# JunctionBoard.net
KiCad netlist of a schematic drawn in EAGLE
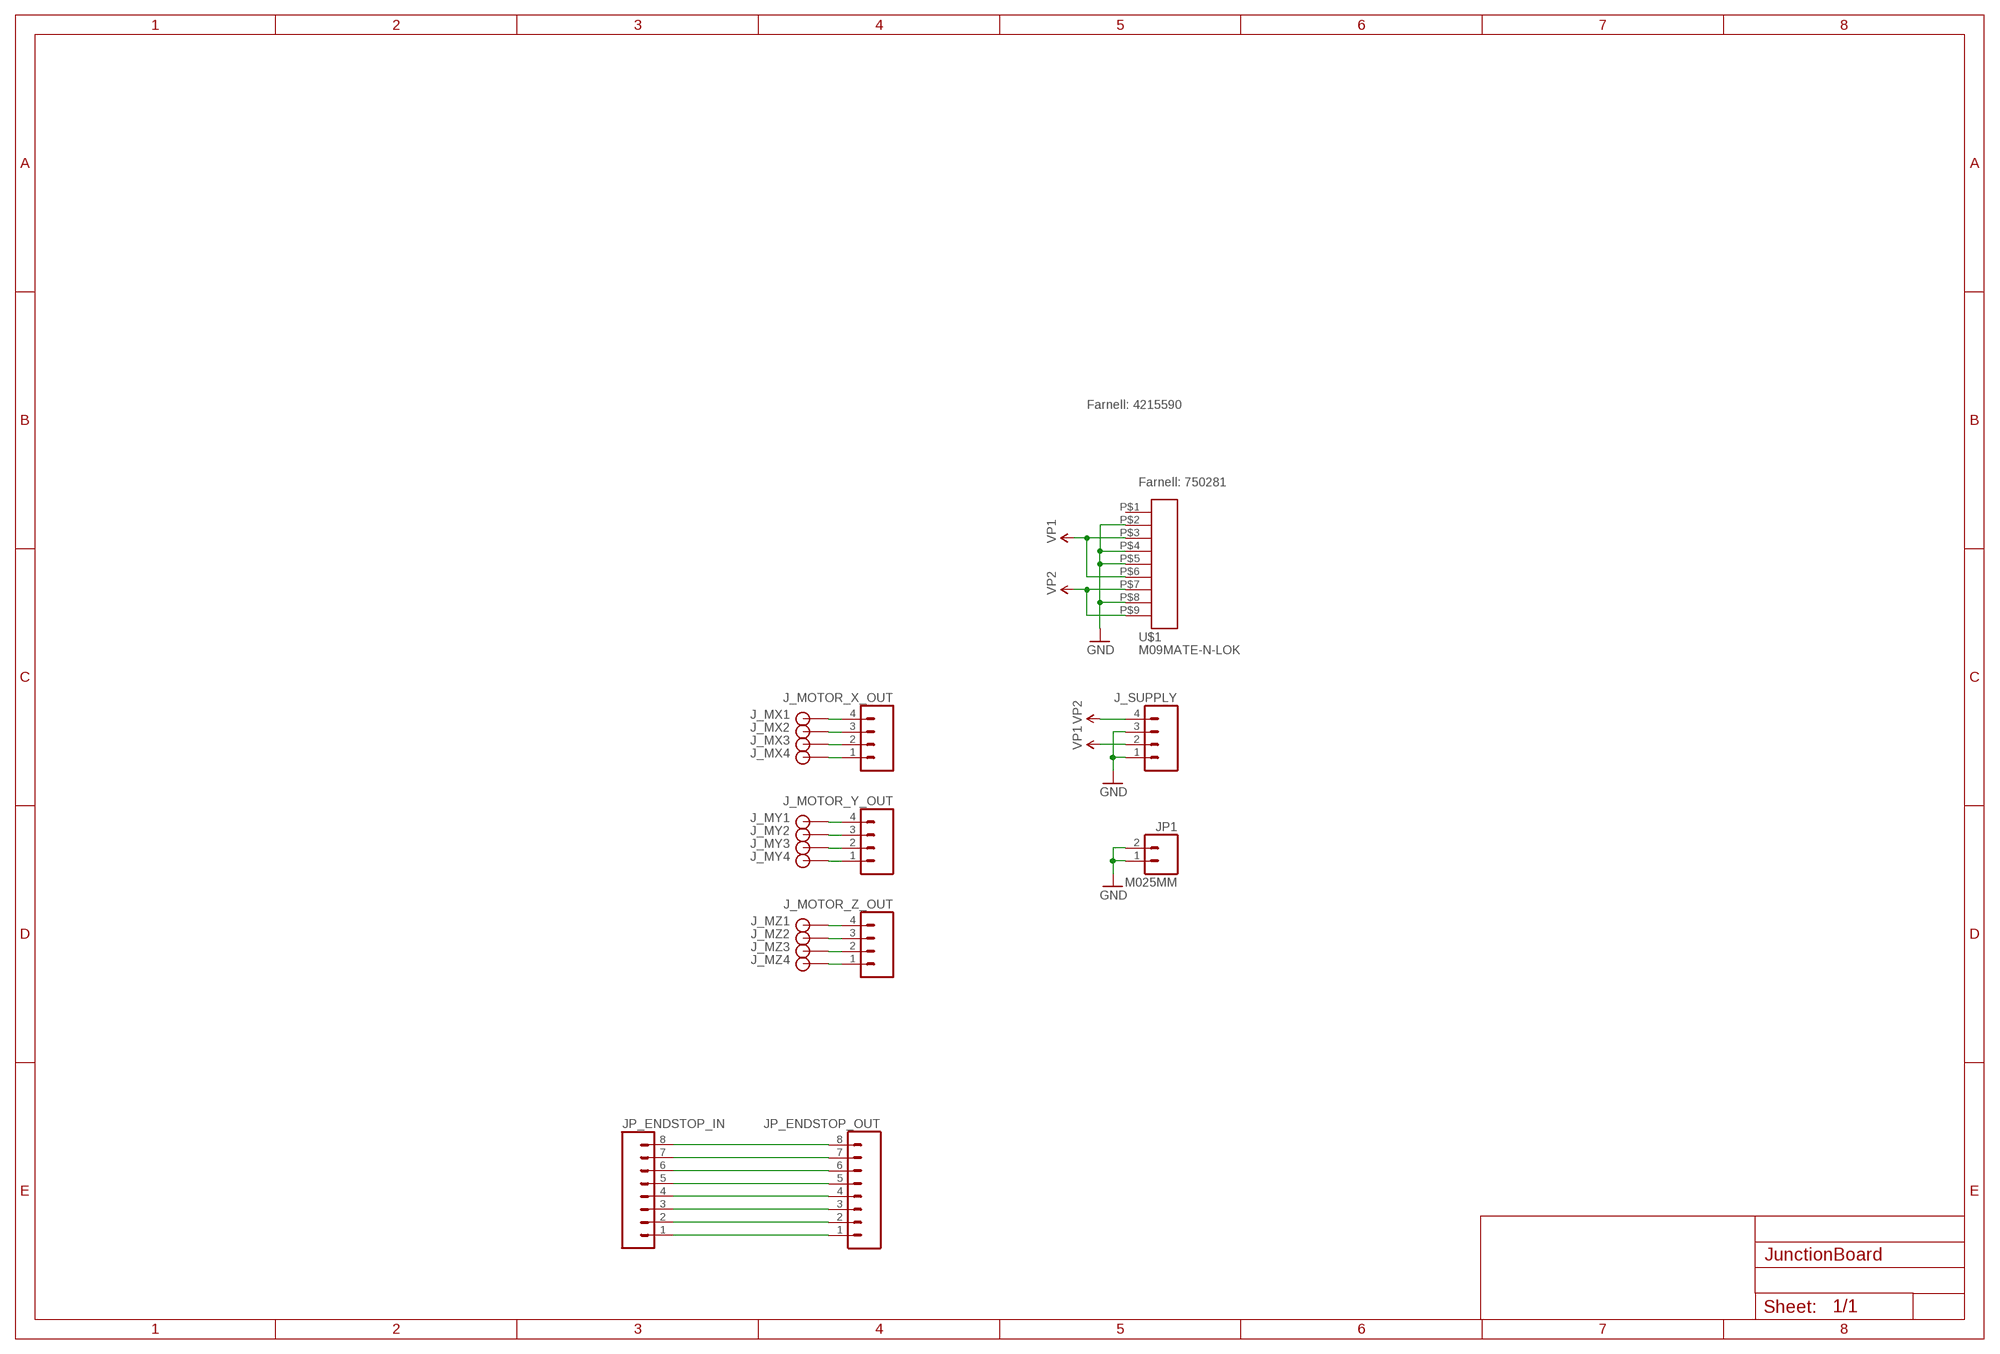
[diagram p0: schematic, sheet 1]

(export (version "E")
  (design (tool "Eeschema 10.0.6"))
  (components
    (comp (ref "JP1")
      (value "M025MM")
      (footprint "eagle-import:SCREWTERMINAL-5MM-2")
      (libsource (lib "eagle-import") (part "M025MM"))
    )
    (comp (ref "JP_ENDSTOP_IN")
      (value "M083.5MM-8")
      (footprint "eagle-import:SCREWTERMINAL-3.5MM-8")
      (libsource (lib "eagle-import") (part "M083.5MM-8"))
    )
    (comp (ref "JP_ENDSTOP_OUT")
      (value "M083.5MM-8")
      (footprint "eagle-import:SCREWTERMINAL-3.5MM-8")
      (libsource (lib "eagle-import") (part "M083.5MM-8"))
    )
    (comp (ref "J_MOTOR_X_OUT")
      (value "M04SCREW5")
      (footprint "eagle-import:SCREWTERMINAL-5MM-4")
      (libsource (lib "eagle-import") (part "M04SCREW5"))
    )
    (comp (ref "J_MOTOR_Y_OUT")
      (value "M04SCREW5")
      (footprint "eagle-import:SCREWTERMINAL-5MM-4")
      (libsource (lib "eagle-import") (part "M04SCREW5"))
    )
    (comp (ref "J_MOTOR_Z_OUT")
      (value "M04SCREW5")
      (footprint "eagle-import:SCREWTERMINAL-5MM-4")
      (libsource (lib "eagle-import") (part "M04SCREW5"))
    )
    (comp (ref "J_MX1")
      (value "M01")
      (footprint "eagle-import:FASTON-1")
      (libsource (lib "eagle-import") (part "M01"))
    )
    (comp (ref "J_MX2")
      (value "M01")
      (footprint "eagle-import:FASTON-1")
      (libsource (lib "eagle-import") (part "M01"))
    )
    (comp (ref "J_MX3")
      (value "M01")
      (footprint "eagle-import:FASTON-1")
      (libsource (lib "eagle-import") (part "M01"))
    )
    (comp (ref "J_MX4")
      (value "M01")
      (footprint "eagle-import:FASTON-1")
      (libsource (lib "eagle-import") (part "M01"))
    )
    (comp (ref "J_MY1")
      (value "M01")
      (footprint "eagle-import:FASTON-1")
      (libsource (lib "eagle-import") (part "M01"))
    )
    (comp (ref "J_MY2")
      (value "M01")
      (footprint "eagle-import:FASTON-1")
      (libsource (lib "eagle-import") (part "M01"))
    )
    (comp (ref "J_MY3")
      (value "M01")
      (footprint "eagle-import:FASTON-1")
      (libsource (lib "eagle-import") (part "M01"))
    )
    (comp (ref "J_MY4")
      (value "M01")
      (footprint "eagle-import:FASTON-1")
      (libsource (lib "eagle-import") (part "M01"))
    )
    (comp (ref "J_MZ1")
      (value "M01")
      (footprint "eagle-import:FASTON-1")
      (libsource (lib "eagle-import") (part "M01"))
    )
    (comp (ref "J_MZ2")
      (value "M01")
      (footprint "eagle-import:FASTON-1")
      (libsource (lib "eagle-import") (part "M01"))
    )
    (comp (ref "J_MZ3")
      (value "M01")
      (footprint "eagle-import:FASTON-1")
      (libsource (lib "eagle-import") (part "M01"))
    )
    (comp (ref "J_MZ4")
      (value "M01")
      (footprint "eagle-import:FASTON-1")
      (libsource (lib "eagle-import") (part "M01"))
    )
    (comp (ref "J_SUPPLY")
      (value "M04SCREW5")
      (footprint "eagle-import:SCREWTERMINAL-5MM-4")
      (libsource (lib "eagle-import") (part "M04SCREW5"))
    )
    (comp (ref "U$1")
      (value "M09MATE-N-LOK")
      (footprint "eagle-import:MATE-N-LOK-9")
      (libsource (lib "eagle-import") (part "M09MATE-N-LOK"))
    )
  )
  (nets
    (net (code "1") (name "GND") (class "Default")
      (node (ref "JP1") (pin "1") (pinfunction "1_1") (pintype "passive"))
      (node (ref "JP1") (pin "2") (pinfunction "2_2") (pintype "passive"))
      (node (ref "J_SUPPLY") (pin "1") (pinfunction "1_1") (pintype "passive"))
      (node (ref "J_SUPPLY") (pin "3") (pinfunction "3_3") (pintype "passive"))
      (node (ref "U$1") (pin "P$2") (pinfunction "P$2_P$2") (pintype "bidirectional"))
      (node (ref "U$1") (pin "P$4") (pinfunction "P$4_P$4") (pintype "bidirectional"))
      (node (ref "U$1") (pin "P$5") (pinfunction "P$5_P$5") (pintype "bidirectional"))
      (node (ref "U$1") (pin "P$8") (pinfunction "P$8_P$8") (pintype "bidirectional"))
    )
    (net (code "2") (name "Net-(JP_ENDSTOP_IN-Pad1)") (class "Default")
      (node (ref "JP_ENDSTOP_IN") (pin "1") (pinfunction "1_1") (pintype "passive"))
      (node (ref "JP_ENDSTOP_OUT") (pin "1") (pinfunction "1_1") (pintype "passive"))
    )
    (net (code "3") (name "Net-(JP_ENDSTOP_IN-Pad2)") (class "Default")
      (node (ref "JP_ENDSTOP_IN") (pin "2") (pinfunction "2_2") (pintype "passive"))
      (node (ref "JP_ENDSTOP_OUT") (pin "2") (pinfunction "2_2") (pintype "passive"))
    )
    (net (code "4") (name "Net-(JP_ENDSTOP_IN-Pad3)") (class "Default")
      (node (ref "JP_ENDSTOP_IN") (pin "3") (pinfunction "3_3") (pintype "passive"))
      (node (ref "JP_ENDSTOP_OUT") (pin "3") (pinfunction "3_3") (pintype "passive"))
    )
    (net (code "5") (name "Net-(JP_ENDSTOP_IN-Pad4)") (class "Default")
      (node (ref "JP_ENDSTOP_IN") (pin "4") (pinfunction "4_4") (pintype "passive"))
      (node (ref "JP_ENDSTOP_OUT") (pin "4") (pinfunction "4_4") (pintype "passive"))
    )
    (net (code "6") (name "Net-(JP_ENDSTOP_IN-Pad5)") (class "Default")
      (node (ref "JP_ENDSTOP_IN") (pin "5") (pinfunction "5_5") (pintype "passive"))
      (node (ref "JP_ENDSTOP_OUT") (pin "5") (pinfunction "5_5") (pintype "passive"))
    )
    (net (code "7") (name "Net-(JP_ENDSTOP_IN-Pad6)") (class "Default")
      (node (ref "JP_ENDSTOP_IN") (pin "6") (pinfunction "6_6") (pintype "passive"))
      (node (ref "JP_ENDSTOP_OUT") (pin "6") (pinfunction "6_6") (pintype "passive"))
    )
    (net (code "8") (name "Net-(JP_ENDSTOP_IN-Pad7)") (class "Default")
      (node (ref "JP_ENDSTOP_IN") (pin "7") (pinfunction "7_7") (pintype "passive"))
      (node (ref "JP_ENDSTOP_OUT") (pin "7") (pinfunction "7_7") (pintype "passive"))
    )
    (net (code "9") (name "Net-(JP_ENDSTOP_IN-Pad8)") (class "Default")
      (node (ref "JP_ENDSTOP_IN") (pin "8") (pinfunction "8_8") (pintype "passive"))
      (node (ref "JP_ENDSTOP_OUT") (pin "8") (pinfunction "8_8") (pintype "passive"))
    )
    (net (code "10") (name "Net-(J_MOTOR_X_OUT-Pad1)") (class "Default")
      (node (ref "J_MOTOR_X_OUT") (pin "1") (pinfunction "1_1") (pintype "passive"))
      (node (ref "J_MX4") (pin "P$1") (pinfunction "P$1_P$1") (pintype "bidirectional"))
      (node (ref "J_MX4") (pin "P$2") (pinfunction "P$1_P$2") (pintype "bidirectional"))
    )
    (net (code "11") (name "Net-(J_MOTOR_X_OUT-Pad2)") (class "Default")
      (node (ref "J_MOTOR_X_OUT") (pin "2") (pinfunction "2_2") (pintype "passive"))
      (node (ref "J_MX3") (pin "P$1") (pinfunction "P$1_P$1") (pintype "bidirectional"))
      (node (ref "J_MX3") (pin "P$2") (pinfunction "P$1_P$2") (pintype "bidirectional"))
    )
    (net (code "12") (name "Net-(J_MOTOR_X_OUT-Pad3)") (class "Default")
      (node (ref "J_MOTOR_X_OUT") (pin "3") (pinfunction "3_3") (pintype "passive"))
      (node (ref "J_MX2") (pin "P$1") (pinfunction "P$1_P$1") (pintype "bidirectional"))
      (node (ref "J_MX2") (pin "P$2") (pinfunction "P$1_P$2") (pintype "bidirectional"))
    )
    (net (code "13") (name "Net-(J_MOTOR_X_OUT-Pad4)") (class "Default")
      (node (ref "J_MOTOR_X_OUT") (pin "4") (pinfunction "4_4") (pintype "passive"))
      (node (ref "J_MX1") (pin "P$1") (pinfunction "P$1_P$1") (pintype "bidirectional"))
      (node (ref "J_MX1") (pin "P$2") (pinfunction "P$1_P$2") (pintype "bidirectional"))
    )
    (net (code "14") (name "Net-(J_MOTOR_Y_OUT-Pad1)") (class "Default")
      (node (ref "J_MOTOR_Y_OUT") (pin "1") (pinfunction "1_1") (pintype "passive"))
      (node (ref "J_MY4") (pin "P$1") (pinfunction "P$1_P$1") (pintype "bidirectional"))
      (node (ref "J_MY4") (pin "P$2") (pinfunction "P$1_P$2") (pintype "bidirectional"))
    )
    (net (code "15") (name "Net-(J_MOTOR_Y_OUT-Pad2)") (class "Default")
      (node (ref "J_MOTOR_Y_OUT") (pin "2") (pinfunction "2_2") (pintype "passive"))
      (node (ref "J_MY3") (pin "P$1") (pinfunction "P$1_P$1") (pintype "bidirectional"))
      (node (ref "J_MY3") (pin "P$2") (pinfunction "P$1_P$2") (pintype "bidirectional"))
    )
    (net (code "16") (name "Net-(J_MOTOR_Y_OUT-Pad3)") (class "Default")
      (node (ref "J_MOTOR_Y_OUT") (pin "3") (pinfunction "3_3") (pintype "passive"))
      (node (ref "J_MY2") (pin "P$1") (pinfunction "P$1_P$1") (pintype "bidirectional"))
      (node (ref "J_MY2") (pin "P$2") (pinfunction "P$1_P$2") (pintype "bidirectional"))
    )
    (net (code "17") (name "Net-(J_MOTOR_Y_OUT-Pad4)") (class "Default")
      (node (ref "J_MOTOR_Y_OUT") (pin "4") (pinfunction "4_4") (pintype "passive"))
      (node (ref "J_MY1") (pin "P$1") (pinfunction "P$1_P$1") (pintype "bidirectional"))
      (node (ref "J_MY1") (pin "P$2") (pinfunction "P$1_P$2") (pintype "bidirectional"))
    )
    (net (code "18") (name "Net-(J_MOTOR_Z_OUT-Pad1)") (class "Default")
      (node (ref "J_MOTOR_Z_OUT") (pin "1") (pinfunction "1_1") (pintype "passive"))
      (node (ref "J_MZ4") (pin "P$1") (pinfunction "P$1_P$1") (pintype "bidirectional"))
      (node (ref "J_MZ4") (pin "P$2") (pinfunction "P$1_P$2") (pintype "bidirectional"))
    )
    (net (code "19") (name "Net-(J_MOTOR_Z_OUT-Pad2)") (class "Default")
      (node (ref "J_MOTOR_Z_OUT") (pin "2") (pinfunction "2_2") (pintype "passive"))
      (node (ref "J_MZ3") (pin "P$1") (pinfunction "P$1_P$1") (pintype "bidirectional"))
      (node (ref "J_MZ3") (pin "P$2") (pinfunction "P$1_P$2") (pintype "bidirectional"))
    )
    (net (code "20") (name "Net-(J_MOTOR_Z_OUT-Pad3)") (class "Default")
      (node (ref "J_MOTOR_Z_OUT") (pin "3") (pinfunction "3_3") (pintype "passive"))
      (node (ref "J_MZ2") (pin "P$1") (pinfunction "P$1_P$1") (pintype "bidirectional"))
      (node (ref "J_MZ2") (pin "P$2") (pinfunction "P$1_P$2") (pintype "bidirectional"))
    )
    (net (code "21") (name "Net-(J_MOTOR_Z_OUT-Pad4)") (class "Default")
      (node (ref "J_MOTOR_Z_OUT") (pin "4") (pinfunction "4_4") (pintype "passive"))
      (node (ref "J_MZ1") (pin "P$1") (pinfunction "P$1_P$1") (pintype "bidirectional"))
      (node (ref "J_MZ1") (pin "P$2") (pinfunction "P$1_P$2") (pintype "bidirectional"))
    )
    (net (code "22") (name "VP1") (class "Default")
      (node (ref "J_SUPPLY") (pin "2") (pinfunction "2_2") (pintype "passive"))
      (node (ref "U$1") (pin "P$3") (pinfunction "P$3_P$3") (pintype "bidirectional"))
      (node (ref "U$1") (pin "P$6") (pinfunction "P$6_P$6") (pintype "bidirectional"))
    )
    (net (code "23") (name "VP2") (class "Default")
      (node (ref "J_SUPPLY") (pin "4") (pinfunction "4_4") (pintype "passive"))
      (node (ref "U$1") (pin "P$7") (pinfunction "P$7_P$7") (pintype "bidirectional"))
      (node (ref "U$1") (pin "P$9") (pinfunction "P$9_P$9") (pintype "bidirectional"))
    )
    (net (code "24") (name "unconnected-(U$1-PadP$1)") (class "Default")
      (node (ref "U$1") (pin "P$1") (pinfunction "P$1_P$1") (pintype "bidirectional"))
    )
  )
)
